# RGB.net
KiCad netlist of a schematic drawn in Altium Designer
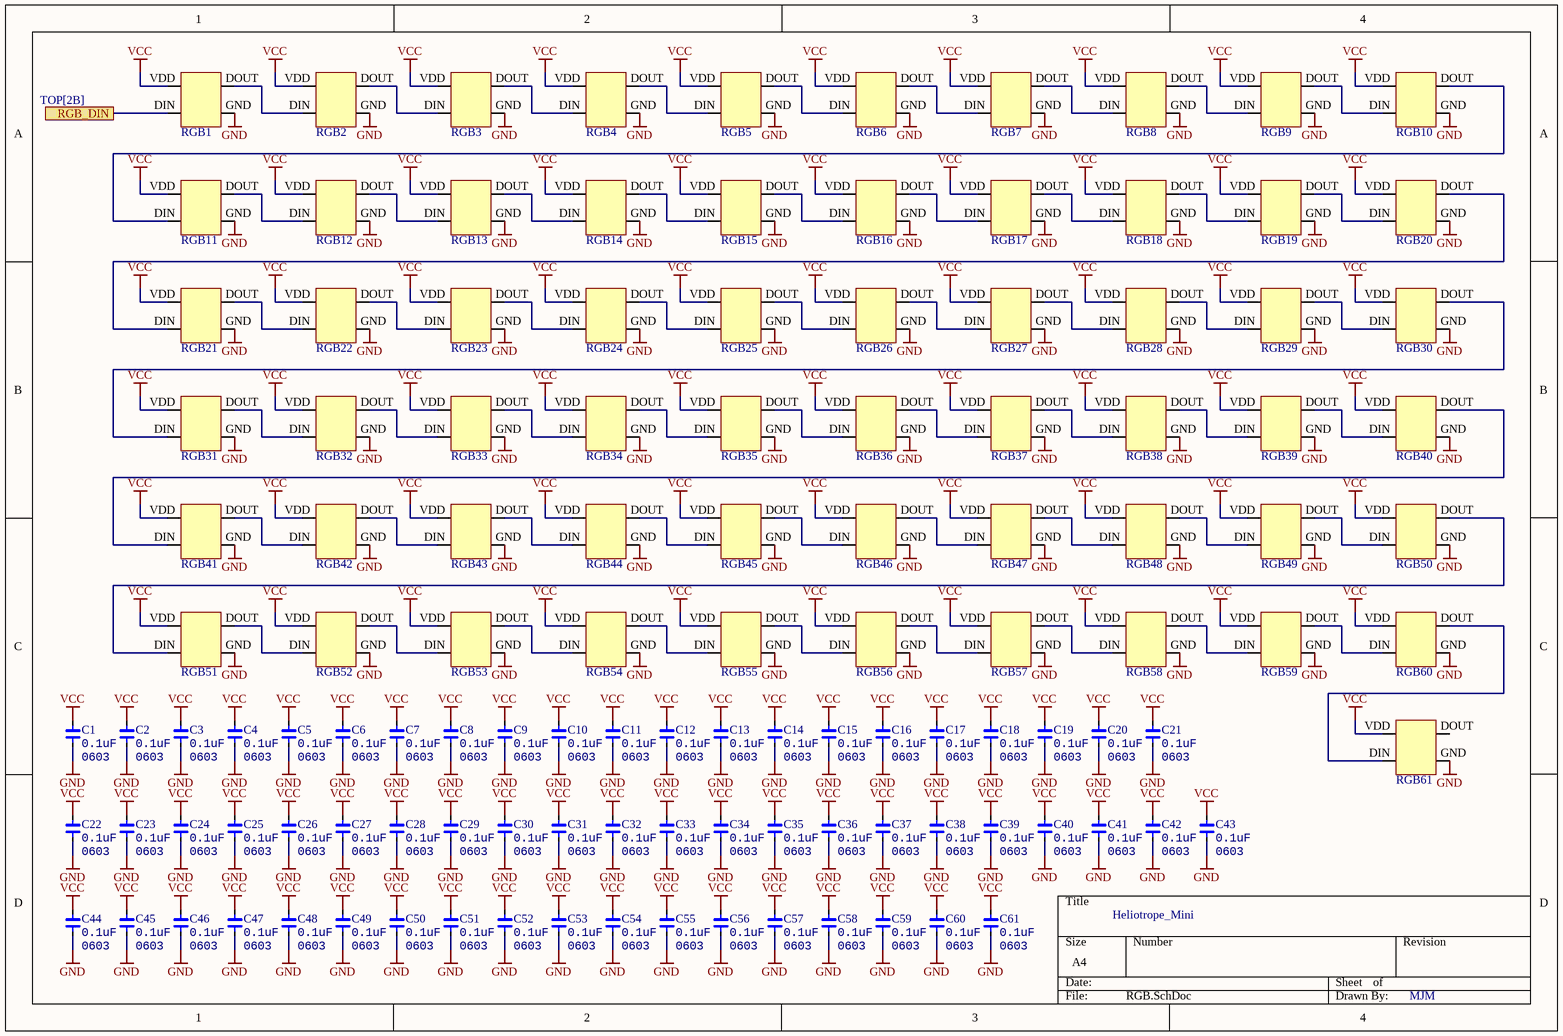
[diagram p0: RGB.SchDoc]

(export (version "E")
  (design (tool "Eeschema 10.0.6"))
  (components
    (comp (ref "C1")
      (value "0.1uF")
      (footprint "FP-CC0603-DA-MFG")
      (description "0603 0.1 uF 50 V ±5 % Tolerance X7R SMT Multilayer Ceramic Capacitor")
      (fields (field (name "TYPE") "0603") (field (name "Comment") "CC0603JRX7R9BB104"))
      (libsource (lib "Microcom Corporation") (part "M_Cap"))
    )
    (comp (ref "C2")
      (value "0.1uF")
      (footprint "FP-CC0603-DA-MFG")
      (description "0603 0.1 uF 50 V ±5 % Tolerance X7R SMT Multilayer Ceramic Capacitor")
      (fields (field (name "TYPE") "0603") (field (name "Comment") "CC0603JRX7R9BB104"))
      (libsource (lib "Microcom Corporation") (part "M_Cap"))
    )
    (comp (ref "C3")
      (value "0.1uF")
      (footprint "FP-CC0603-DA-MFG")
      (description "0603 0.1 uF 50 V ±5 % Tolerance X7R SMT Multilayer Ceramic Capacitor")
      (fields (field (name "TYPE") "0603") (field (name "Comment") "CC0603JRX7R9BB104"))
      (libsource (lib "Microcom Corporation") (part "M_Cap"))
    )
    (comp (ref "C4")
      (value "0.1uF")
      (footprint "FP-CC0603-DA-MFG")
      (description "0603 0.1 uF 50 V ±5 % Tolerance X7R SMT Multilayer Ceramic Capacitor")
      (fields (field (name "TYPE") "0603") (field (name "Comment") "CC0603JRX7R9BB104"))
      (libsource (lib "Microcom Corporation") (part "M_Cap"))
    )
    (comp (ref "C5")
      (value "0.1uF")
      (footprint "FP-CC0603-DA-MFG")
      (description "0603 0.1 uF 50 V ±5 % Tolerance X7R SMT Multilayer Ceramic Capacitor")
      (fields (field (name "TYPE") "0603") (field (name "Comment") "CC0603JRX7R9BB104"))
      (libsource (lib "Microcom Corporation") (part "M_Cap"))
    )
    (comp (ref "C6")
      (value "0.1uF")
      (footprint "FP-CC0603-DA-MFG")
      (description "0603 0.1 uF 50 V ±5 % Tolerance X7R SMT Multilayer Ceramic Capacitor")
      (fields (field (name "TYPE") "0603") (field (name "Comment") "CC0603JRX7R9BB104"))
      (libsource (lib "Microcom Corporation") (part "M_Cap"))
    )
    (comp (ref "C7")
      (value "0.1uF")
      (footprint "FP-CC0603-DA-MFG")
      (description "0603 0.1 uF 50 V ±5 % Tolerance X7R SMT Multilayer Ceramic Capacitor")
      (fields (field (name "TYPE") "0603") (field (name "Comment") "CC0603JRX7R9BB104"))
      (libsource (lib "Microcom Corporation") (part "M_Cap"))
    )
    (comp (ref "C8")
      (value "0.1uF")
      (footprint "FP-CC0603-DA-MFG")
      (description "0603 0.1 uF 50 V ±5 % Tolerance X7R SMT Multilayer Ceramic Capacitor")
      (fields (field (name "TYPE") "0603") (field (name "Comment") "CC0603JRX7R9BB104"))
      (libsource (lib "Microcom Corporation") (part "M_Cap"))
    )
    (comp (ref "C9")
      (value "0.1uF")
      (footprint "FP-CC0603-DA-MFG")
      (description "0603 0.1 uF 50 V ±5 % Tolerance X7R SMT Multilayer Ceramic Capacitor")
      (fields (field (name "TYPE") "0603") (field (name "Comment") "CC0603JRX7R9BB104"))
      (libsource (lib "Microcom Corporation") (part "M_Cap"))
    )
    (comp (ref "C10")
      (value "0.1uF")
      (footprint "FP-CC0603-DA-MFG")
      (description "0603 0.1 uF 50 V ±5 % Tolerance X7R SMT Multilayer Ceramic Capacitor")
      (fields (field (name "TYPE") "0603") (field (name "Comment") "CC0603JRX7R9BB104"))
      (libsource (lib "Microcom Corporation") (part "M_Cap"))
    )
    (comp (ref "C11")
      (value "0.1uF")
      (footprint "FP-CC0603-DA-MFG")
      (description "0603 0.1 uF 50 V ±5 % Tolerance X7R SMT Multilayer Ceramic Capacitor")
      (fields (field (name "TYPE") "0603") (field (name "Comment") "CC0603JRX7R9BB104"))
      (libsource (lib "Microcom Corporation") (part "M_Cap"))
    )
    (comp (ref "C12")
      (value "0.1uF")
      (footprint "FP-CC0603-DA-MFG")
      (description "0603 0.1 uF 50 V ±5 % Tolerance X7R SMT Multilayer Ceramic Capacitor")
      (fields (field (name "TYPE") "0603") (field (name "Comment") "CC0603JRX7R9BB104"))
      (libsource (lib "Microcom Corporation") (part "M_Cap"))
    )
    (comp (ref "C13")
      (value "0.1uF")
      (footprint "FP-CC0603-DA-MFG")
      (description "0603 0.1 uF 50 V ±5 % Tolerance X7R SMT Multilayer Ceramic Capacitor")
      (fields (field (name "TYPE") "0603") (field (name "Comment") "CC0603JRX7R9BB104"))
      (libsource (lib "Microcom Corporation") (part "M_Cap"))
    )
    (comp (ref "C14")
      (value "0.1uF")
      (footprint "FP-CC0603-DA-MFG")
      (description "0603 0.1 uF 50 V ±5 % Tolerance X7R SMT Multilayer Ceramic Capacitor")
      (fields (field (name "TYPE") "0603") (field (name "Comment") "CC0603JRX7R9BB104"))
      (libsource (lib "Microcom Corporation") (part "M_Cap"))
    )
    (comp (ref "C15")
      (value "0.1uF")
      (footprint "FP-CC0603-DA-MFG")
      (description "0603 0.1 uF 50 V ±5 % Tolerance X7R SMT Multilayer Ceramic Capacitor")
      (fields (field (name "TYPE") "0603") (field (name "Comment") "CC0603JRX7R9BB104"))
      (libsource (lib "Microcom Corporation") (part "M_Cap"))
    )
    (comp (ref "C16")
      (value "0.1uF")
      (footprint "FP-CC0603-DA-MFG")
      (description "0603 0.1 uF 50 V ±5 % Tolerance X7R SMT Multilayer Ceramic Capacitor")
      (fields (field (name "TYPE") "0603") (field (name "Comment") "CC0603JRX7R9BB104"))
      (libsource (lib "Microcom Corporation") (part "M_Cap"))
    )
    (comp (ref "C17")
      (value "0.1uF")
      (footprint "FP-CC0603-DA-MFG")
      (description "0603 0.1 uF 50 V ±5 % Tolerance X7R SMT Multilayer Ceramic Capacitor")
      (fields (field (name "TYPE") "0603") (field (name "Comment") "CC0603JRX7R9BB104"))
      (libsource (lib "Microcom Corporation") (part "M_Cap"))
    )
    (comp (ref "C18")
      (value "0.1uF")
      (footprint "FP-CC0603-DA-MFG")
      (description "0603 0.1 uF 50 V ±5 % Tolerance X7R SMT Multilayer Ceramic Capacitor")
      (fields (field (name "TYPE") "0603") (field (name "Comment") "CC0603JRX7R9BB104"))
      (libsource (lib "Microcom Corporation") (part "M_Cap"))
    )
    (comp (ref "C19")
      (value "0.1uF")
      (footprint "FP-CC0603-DA-MFG")
      (description "0603 0.1 uF 50 V ±5 % Tolerance X7R SMT Multilayer Ceramic Capacitor")
      (fields (field (name "TYPE") "0603") (field (name "Comment") "CC0603JRX7R9BB104"))
      (libsource (lib "Microcom Corporation") (part "M_Cap"))
    )
    (comp (ref "C20")
      (value "0.1uF")
      (footprint "FP-CC0603-DA-MFG")
      (description "0603 0.1 uF 50 V ±5 % Tolerance X7R SMT Multilayer Ceramic Capacitor")
      (fields (field (name "TYPE") "0603") (field (name "Comment") "CC0603JRX7R9BB104"))
      (libsource (lib "Microcom Corporation") (part "M_Cap"))
    )
    (comp (ref "C21")
      (value "0.1uF")
      (footprint "FP-CC0603-DA-MFG")
      (description "0603 0.1 uF 50 V ±5 % Tolerance X7R SMT Multilayer Ceramic Capacitor")
      (fields (field (name "TYPE") "0603") (field (name "Comment") "CC0603JRX7R9BB104"))
      (libsource (lib "Microcom Corporation") (part "M_Cap"))
    )
    (comp (ref "C22")
      (value "0.1uF")
      (footprint "FP-CC0603-DA-MFG")
      (description "0603 0.1 uF 50 V ±5 % Tolerance X7R SMT Multilayer Ceramic Capacitor")
      (fields (field (name "TYPE") "0603") (field (name "Comment") "CC0603JRX7R9BB104"))
      (libsource (lib "Microcom Corporation") (part "M_Cap"))
    )
    (comp (ref "C23")
      (value "0.1uF")
      (footprint "FP-CC0603-DA-MFG")
      (description "0603 0.1 uF 50 V ±5 % Tolerance X7R SMT Multilayer Ceramic Capacitor")
      (fields (field (name "TYPE") "0603") (field (name "Comment") "CC0603JRX7R9BB104"))
      (libsource (lib "Microcom Corporation") (part "M_Cap"))
    )
    (comp (ref "C24")
      (value "0.1uF")
      (footprint "FP-CC0603-DA-MFG")
      (description "0603 0.1 uF 50 V ±5 % Tolerance X7R SMT Multilayer Ceramic Capacitor")
      (fields (field (name "TYPE") "0603") (field (name "Comment") "CC0603JRX7R9BB104"))
      (libsource (lib "Microcom Corporation") (part "M_Cap"))
    )
    (comp (ref "C25")
      (value "0.1uF")
      (footprint "FP-CC0603-DA-MFG")
      (description "0603 0.1 uF 50 V ±5 % Tolerance X7R SMT Multilayer Ceramic Capacitor")
      (fields (field (name "TYPE") "0603") (field (name "Comment") "CC0603JRX7R9BB104"))
      (libsource (lib "Microcom Corporation") (part "M_Cap"))
    )
    (comp (ref "C26")
      (value "0.1uF")
      (footprint "FP-CC0603-DA-MFG")
      (description "0603 0.1 uF 50 V ±5 % Tolerance X7R SMT Multilayer Ceramic Capacitor")
      (fields (field (name "TYPE") "0603") (field (name "Comment") "CC0603JRX7R9BB104"))
      (libsource (lib "Microcom Corporation") (part "M_Cap"))
    )
    (comp (ref "C27")
      (value "0.1uF")
      (footprint "FP-CC0603-DA-MFG")
      (description "0603 0.1 uF 50 V ±5 % Tolerance X7R SMT Multilayer Ceramic Capacitor")
      (fields (field (name "TYPE") "0603") (field (name "Comment") "CC0603JRX7R9BB104"))
      (libsource (lib "Microcom Corporation") (part "M_Cap"))
    )
    (comp (ref "C28")
      (value "0.1uF")
      (footprint "FP-CC0603-DA-MFG")
      (description "0603 0.1 uF 50 V ±5 % Tolerance X7R SMT Multilayer Ceramic Capacitor")
      (fields (field (name "TYPE") "0603") (field (name "Comment") "CC0603JRX7R9BB104"))
      (libsource (lib "Microcom Corporation") (part "M_Cap"))
    )
    (comp (ref "C29")
      (value "0.1uF")
      (footprint "FP-CC0603-DA-MFG")
      (description "0603 0.1 uF 50 V ±5 % Tolerance X7R SMT Multilayer Ceramic Capacitor")
      (fields (field (name "TYPE") "0603") (field (name "Comment") "CC0603JRX7R9BB104"))
      (libsource (lib "Microcom Corporation") (part "M_Cap"))
    )
    (comp (ref "C30")
      (value "0.1uF")
      (footprint "FP-CC0603-DA-MFG")
      (description "0603 0.1 uF 50 V ±5 % Tolerance X7R SMT Multilayer Ceramic Capacitor")
      (fields (field (name "TYPE") "0603") (field (name "Comment") "CC0603JRX7R9BB104"))
      (libsource (lib "Microcom Corporation") (part "M_Cap"))
    )
    (comp (ref "C31")
      (value "0.1uF")
      (footprint "FP-CC0603-DA-MFG")
      (description "0603 0.1 uF 50 V ±5 % Tolerance X7R SMT Multilayer Ceramic Capacitor")
      (fields (field (name "TYPE") "0603") (field (name "Comment") "CC0603JRX7R9BB104"))
      (libsource (lib "Microcom Corporation") (part "M_Cap"))
    )
    (comp (ref "C32")
      (value "0.1uF")
      (footprint "FP-CC0603-DA-MFG")
      (description "0603 0.1 uF 50 V ±5 % Tolerance X7R SMT Multilayer Ceramic Capacitor")
      (fields (field (name "TYPE") "0603") (field (name "Comment") "CC0603JRX7R9BB104"))
      (libsource (lib "Microcom Corporation") (part "M_Cap"))
    )
    (comp (ref "C33")
      (value "0.1uF")
      (footprint "FP-CC0603-DA-MFG")
      (description "0603 0.1 uF 50 V ±5 % Tolerance X7R SMT Multilayer Ceramic Capacitor")
      (fields (field (name "TYPE") "0603") (field (name "Comment") "CC0603JRX7R9BB104"))
      (libsource (lib "Microcom Corporation") (part "M_Cap"))
    )
    (comp (ref "C34")
      (value "0.1uF")
      (footprint "FP-CC0603-DA-MFG")
      (description "0603 0.1 uF 50 V ±5 % Tolerance X7R SMT Multilayer Ceramic Capacitor")
      (fields (field (name "TYPE") "0603") (field (name "Comment") "CC0603JRX7R9BB104"))
      (libsource (lib "Microcom Corporation") (part "M_Cap"))
    )
    (comp (ref "C35")
      (value "0.1uF")
      (footprint "FP-CC0603-DA-MFG")
      (description "0603 0.1 uF 50 V ±5 % Tolerance X7R SMT Multilayer Ceramic Capacitor")
      (fields (field (name "TYPE") "0603") (field (name "Comment") "CC0603JRX7R9BB104"))
      (libsource (lib "Microcom Corporation") (part "M_Cap"))
    )
    (comp (ref "C36")
      (value "0.1uF")
      (footprint "FP-CC0603-DA-MFG")
      (description "0603 0.1 uF 50 V ±5 % Tolerance X7R SMT Multilayer Ceramic Capacitor")
      (fields (field (name "TYPE") "0603") (field (name "Comment") "CC0603JRX7R9BB104"))
      (libsource (lib "Microcom Corporation") (part "M_Cap"))
    )
    (comp (ref "C37")
      (value "0.1uF")
      (footprint "FP-CC0603-DA-MFG")
      (description "0603 0.1 uF 50 V ±5 % Tolerance X7R SMT Multilayer Ceramic Capacitor")
      (fields (field (name "TYPE") "0603") (field (name "Comment") "CC0603JRX7R9BB104"))
      (libsource (lib "Microcom Corporation") (part "M_Cap"))
    )
    (comp (ref "C38")
      (value "0.1uF")
      (footprint "FP-CC0603-DA-MFG")
      (description "0603 0.1 uF 50 V ±5 % Tolerance X7R SMT Multilayer Ceramic Capacitor")
      (fields (field (name "TYPE") "0603") (field (name "Comment") "CC0603JRX7R9BB104"))
      (libsource (lib "Microcom Corporation") (part "M_Cap"))
    )
    (comp (ref "C39")
      (value "0.1uF")
      (footprint "FP-CC0603-DA-MFG")
      (description "0603 0.1 uF 50 V ±5 % Tolerance X7R SMT Multilayer Ceramic Capacitor")
      (fields (field (name "TYPE") "0603") (field (name "Comment") "CC0603JRX7R9BB104"))
      (libsource (lib "Microcom Corporation") (part "M_Cap"))
    )
    (comp (ref "C40")
      (value "0.1uF")
      (footprint "FP-CC0603-DA-MFG")
      (description "0603 0.1 uF 50 V ±5 % Tolerance X7R SMT Multilayer Ceramic Capacitor")
      (fields (field (name "TYPE") "0603") (field (name "Comment") "CC0603JRX7R9BB104"))
      (libsource (lib "Microcom Corporation") (part "M_Cap"))
    )
    (comp (ref "C41")
      (value "0.1uF")
      (footprint "FP-CC0603-DA-MFG")
      (description "0603 0.1 uF 50 V ±5 % Tolerance X7R SMT Multilayer Ceramic Capacitor")
      (fields (field (name "TYPE") "0603") (field (name "Comment") "CC0603JRX7R9BB104"))
      (libsource (lib "Microcom Corporation") (part "M_Cap"))
    )
    (comp (ref "C42")
      (value "0.1uF")
      (footprint "FP-CC0603-DA-MFG")
      (description "0603 0.1 uF 50 V ±5 % Tolerance X7R SMT Multilayer Ceramic Capacitor")
      (fields (field (name "TYPE") "0603") (field (name "Comment") "CC0603JRX7R9BB104"))
      (libsource (lib "Microcom Corporation") (part "M_Cap"))
    )
    (comp (ref "C43")
      (value "0.1uF")
      (footprint "FP-CC0603-DA-MFG")
      (description "0603 0.1 uF 50 V ±5 % Tolerance X7R SMT Multilayer Ceramic Capacitor")
      (fields (field (name "TYPE") "0603") (field (name "Comment") "CC0603JRX7R9BB104"))
      (libsource (lib "Microcom Corporation") (part "M_Cap"))
    )
    (comp (ref "C44")
      (value "0.1uF")
      (footprint "FP-CC0603-DA-MFG")
      (description "0603 0.1 uF 50 V ±5 % Tolerance X7R SMT Multilayer Ceramic Capacitor")
      (fields (field (name "TYPE") "0603") (field (name "Comment") "CC0603JRX7R9BB104"))
      (libsource (lib "Microcom Corporation") (part "M_Cap"))
    )
    (comp (ref "C45")
      (value "0.1uF")
      (footprint "FP-CC0603-DA-MFG")
      (description "0603 0.1 uF 50 V ±5 % Tolerance X7R SMT Multilayer Ceramic Capacitor")
      (fields (field (name "TYPE") "0603") (field (name "Comment") "CC0603JRX7R9BB104"))
      (libsource (lib "Microcom Corporation") (part "M_Cap"))
    )
    (comp (ref "C46")
      (value "0.1uF")
      (footprint "FP-CC0603-DA-MFG")
      (description "0603 0.1 uF 50 V ±5 % Tolerance X7R SMT Multilayer Ceramic Capacitor")
      (fields (field (name "TYPE") "0603") (field (name "Comment") "CC0603JRX7R9BB104"))
      (libsource (lib "Microcom Corporation") (part "M_Cap"))
    )
    (comp (ref "C47")
      (value "0.1uF")
      (footprint "FP-CC0603-DA-MFG")
      (description "0603 0.1 uF 50 V ±5 % Tolerance X7R SMT Multilayer Ceramic Capacitor")
      (fields (field (name "TYPE") "0603") (field (name "Comment") "CC0603JRX7R9BB104"))
      (libsource (lib "Microcom Corporation") (part "M_Cap"))
    )
    (comp (ref "C48")
      (value "0.1uF")
      (footprint "FP-CC0603-DA-MFG")
      (description "0603 0.1 uF 50 V ±5 % Tolerance X7R SMT Multilayer Ceramic Capacitor")
      (fields (field (name "TYPE") "0603") (field (name "Comment") "CC0603JRX7R9BB104"))
      (libsource (lib "Microcom Corporation") (part "M_Cap"))
    )
    (comp (ref "C49")
      (value "0.1uF")
      (footprint "FP-CC0603-DA-MFG")
      (description "0603 0.1 uF 50 V ±5 % Tolerance X7R SMT Multilayer Ceramic Capacitor")
      (fields (field (name "TYPE") "0603") (field (name "Comment") "CC0603JRX7R9BB104"))
      (libsource (lib "Microcom Corporation") (part "M_Cap"))
    )
    (comp (ref "C50")
      (value "0.1uF")
      (footprint "FP-CC0603-DA-MFG")
      (description "0603 0.1 uF 50 V ±5 % Tolerance X7R SMT Multilayer Ceramic Capacitor")
      (fields (field (name "TYPE") "0603") (field (name "Comment") "CC0603JRX7R9BB104"))
      (libsource (lib "Microcom Corporation") (part "M_Cap"))
    )
    (comp (ref "C51")
      (value "0.1uF")
      (footprint "FP-CC0603-DA-MFG")
      (description "0603 0.1 uF 50 V ±5 % Tolerance X7R SMT Multilayer Ceramic Capacitor")
      (fields (field (name "TYPE") "0603") (field (name "Comment") "CC0603JRX7R9BB104"))
      (libsource (lib "Microcom Corporation") (part "M_Cap"))
    )
    (comp (ref "C52")
      (value "0.1uF")
      (footprint "FP-CC0603-DA-MFG")
      (description "0603 0.1 uF 50 V ±5 % Tolerance X7R SMT Multilayer Ceramic Capacitor")
      (fields (field (name "TYPE") "0603") (field (name "Comment") "CC0603JRX7R9BB104"))
      (libsource (lib "Microcom Corporation") (part "M_Cap"))
    )
    (comp (ref "C53")
      (value "0.1uF")
      (footprint "FP-CC0603-DA-MFG")
      (description "0603 0.1 uF 50 V ±5 % Tolerance X7R SMT Multilayer Ceramic Capacitor")
      (fields (field (name "TYPE") "0603") (field (name "Comment") "CC0603JRX7R9BB104"))
      (libsource (lib "Microcom Corporation") (part "M_Cap"))
    )
    (comp (ref "C54")
      (value "0.1uF")
      (footprint "FP-CC0603-DA-MFG")
      (description "0603 0.1 uF 50 V ±5 % Tolerance X7R SMT Multilayer Ceramic Capacitor")
      (fields (field (name "TYPE") "0603") (field (name "Comment") "CC0603JRX7R9BB104"))
      (libsource (lib "Microcom Corporation") (part "M_Cap"))
    )
    (comp (ref "C55")
      (value "0.1uF")
      (footprint "FP-CC0603-DA-MFG")
      (description "0603 0.1 uF 50 V ±5 % Tolerance X7R SMT Multilayer Ceramic Capacitor")
      (fields (field (name "TYPE") "0603") (field (name "Comment") "CC0603JRX7R9BB104"))
      (libsource (lib "Microcom Corporation") (part "M_Cap"))
    )
    (comp (ref "C56")
      (value "0.1uF")
      (footprint "FP-CC0603-DA-MFG")
      (description "0603 0.1 uF 50 V ±5 % Tolerance X7R SMT Multilayer Ceramic Capacitor")
      (fields (field (name "TYPE") "0603") (field (name "Comment") "CC0603JRX7R9BB104"))
      (libsource (lib "Microcom Corporation") (part "M_Cap"))
    )
    (comp (ref "C57")
      (value "0.1uF")
      (footprint "FP-CC0603-DA-MFG")
      (description "0603 0.1 uF 50 V ±5 % Tolerance X7R SMT Multilayer Ceramic Capacitor")
      (fields (field (name "TYPE") "0603") (field (name "Comment") "CC0603JRX7R9BB104"))
      (libsource (lib "Microcom Corporation") (part "M_Cap"))
    )
    (comp (ref "C58")
      (value "0.1uF")
      (footprint "FP-CC0603-DA-MFG")
      (description "0603 0.1 uF 50 V ±5 % Tolerance X7R SMT Multilayer Ceramic Capacitor")
      (fields (field (name "TYPE") "0603") (field (name "Comment") "CC0603JRX7R9BB104"))
      (libsource (lib "Microcom Corporation") (part "M_Cap"))
    )
    (comp (ref "C59")
      (value "0.1uF")
      (footprint "FP-CC0603-DA-MFG")
      (description "0603 0.1 uF 50 V ±5 % Tolerance X7R SMT Multilayer Ceramic Capacitor")
      (fields (field (name "TYPE") "0603") (field (name "Comment") "CC0603JRX7R9BB104"))
      (libsource (lib "Microcom Corporation") (part "M_Cap"))
    )
    (comp (ref "C60")
      (value "0.1uF")
      (footprint "FP-CC0603-DA-MFG")
      (description "0603 0.1 uF 50 V ±5 % Tolerance X7R SMT Multilayer Ceramic Capacitor")
      (fields (field (name "TYPE") "0603") (field (name "Comment") "CC0603JRX7R9BB104"))
      (libsource (lib "Microcom Corporation") (part "M_Cap"))
    )
    (comp (ref "C61")
      (value "0.1uF")
      (footprint "FP-CC0603-DA-MFG")
      (description "0603 0.1 uF 50 V ±5 % Tolerance X7R SMT Multilayer Ceramic Capacitor")
      (fields (field (name "TYPE") "0603") (field (name "Comment") "CC0603JRX7R9BB104"))
      (libsource (lib "Microcom Corporation") (part "M_Cap"))
    )
    (comp (ref "RGB1")
      (value "SK6812MINI-E")
      (footprint "sk6812minie")
      (libsource (lib "Microcom Corporation") (part "SK6812MINI-E"))
    )
    (comp (ref "RGB2")
      (value "SK6812MINI-E")
      (footprint "sk6812minie")
      (libsource (lib "Microcom Corporation") (part "SK6812MINI-E"))
    )
    (comp (ref "RGB3")
      (value "SK6812MINI-E")
      (footprint "sk6812minie")
      (libsource (lib "Microcom Corporation") (part "SK6812MINI-E"))
    )
    (comp (ref "RGB4")
      (value "SK6812MINI-E")
      (footprint "sk6812minie")
      (libsource (lib "Microcom Corporation") (part "SK6812MINI-E"))
    )
    (comp (ref "RGB5")
      (value "SK6812MINI-E")
      (footprint "sk6812minie")
      (libsource (lib "Microcom Corporation") (part "SK6812MINI-E"))
    )
    (comp (ref "RGB6")
      (value "SK6812MINI-E")
      (footprint "sk6812minie")
      (libsource (lib "Microcom Corporation") (part "SK6812MINI-E"))
    )
    (comp (ref "RGB7")
      (value "SK6812MINI-E")
      (footprint "sk6812minie")
      (libsource (lib "Microcom Corporation") (part "SK6812MINI-E"))
    )
    (comp (ref "RGB8")
      (value "SK6812MINI-E")
      (footprint "sk6812minie")
      (libsource (lib "Microcom Corporation") (part "SK6812MINI-E"))
    )
    (comp (ref "RGB9")
      (value "SK6812MINI-E")
      (footprint "sk6812minie")
      (libsource (lib "Microcom Corporation") (part "SK6812MINI-E"))
    )
    (comp (ref "RGB10")
      (value "SK6812MINI-E")
      (footprint "sk6812minie")
      (libsource (lib "Microcom Corporation") (part "SK6812MINI-E"))
    )
    (comp (ref "RGB11")
      (value "SK6812MINI-E")
      (footprint "sk6812minie")
      (libsource (lib "Microcom Corporation") (part "SK6812MINI-E"))
    )
    (comp (ref "RGB12")
      (value "SK6812MINI-E")
      (footprint "sk6812minie")
      (libsource (lib "Microcom Corporation") (part "SK6812MINI-E"))
    )
    (comp (ref "RGB13")
      (value "SK6812MINI-E")
      (footprint "sk6812minie")
      (libsource (lib "Microcom Corporation") (part "SK6812MINI-E"))
    )
    (comp (ref "RGB14")
      (value "SK6812MINI-E")
      (footprint "sk6812minie")
      (libsource (lib "Microcom Corporation") (part "SK6812MINI-E"))
    )
    (comp (ref "RGB15")
      (value "SK6812MINI-E")
      (footprint "sk6812minie")
      (libsource (lib "Microcom Corporation") (part "SK6812MINI-E"))
    )
    (comp (ref "RGB16")
      (value "SK6812MINI-E")
      (footprint "sk6812minie")
      (libsource (lib "Microcom Corporation") (part "SK6812MINI-E"))
    )
    (comp (ref "RGB17")
      (value "SK6812MINI-E")
      (footprint "sk6812minie")
      (libsource (lib "Microcom Corporation") (part "SK6812MINI-E"))
    )
    (comp (ref "RGB18")
      (value "SK6812MINI-E")
      (footprint "sk6812minie")
      (libsource (lib "Microcom Corporation") (part "SK6812MINI-E"))
    )
    (comp (ref "RGB19")
      (value "SK6812MINI-E")
      (footprint "sk6812minie")
      (libsource (lib "Microcom Corporation") (part "SK6812MINI-E"))
    )
    (comp (ref "RGB20")
      (value "SK6812MINI-E")
      (footprint "sk6812minie")
      (libsource (lib "Microcom Corporation") (part "SK6812MINI-E"))
    )
    (comp (ref "RGB21")
      (value "SK6812MINI-E")
      (footprint "sk6812minie")
      (libsource (lib "Microcom Corporation") (part "SK6812MINI-E"))
    )
    (comp (ref "RGB22")
      (value "SK6812MINI-E")
      (footprint "sk6812minie")
      (libsource (lib "Microcom Corporation") (part "SK6812MINI-E"))
    )
    (comp (ref "RGB23")
      (value "SK6812MINI-E")
      (footprint "sk6812minie")
      (libsource (lib "Microcom Corporation") (part "SK6812MINI-E"))
    )
    (comp (ref "RGB24")
      (value "SK6812MINI-E")
      (footprint "sk6812minie")
      (libsource (lib "Microcom Corporation") (part "SK6812MINI-E"))
    )
    (comp (ref "RGB25")
      (value "SK6812MINI-E")
      (footprint "sk6812minie")
      (libsource (lib "Microcom Corporation") (part "SK6812MINI-E"))
    )
    (comp (ref "RGB26")
      (value "SK6812MINI-E")
      (footprint "sk6812minie")
      (libsource (lib "Microcom Corporation") (part "SK6812MINI-E"))
    )
    (comp (ref "RGB27")
      (value "SK6812MINI-E")
      (footprint "sk6812minie")
      (libsource (lib "Microcom Corporation") (part "SK6812MINI-E"))
    )
    (comp (ref "RGB28")
      (value "SK6812MINI-E")
      (footprint "sk6812minie")
      (libsource (lib "Microcom Corporation") (part "SK6812MINI-E"))
    )
    (comp (ref "RGB29")
      (value "SK6812MINI-E")
      (footprint "sk6812minie")
      (libsource (lib "Microcom Corporation") (part "SK6812MINI-E"))
    )
    (comp (ref "RGB30")
      (value "SK6812MINI-E")
      (footprint "sk6812minie")
      (libsource (lib "Microcom Corporation") (part "SK6812MINI-E"))
    )
    (comp (ref "RGB31")
      (value "SK6812MINI-E")
      (footprint "sk6812minie")
      (libsource (lib "Microcom Corporation") (part "SK6812MINI-E"))
    )
    (comp (ref "RGB32")
      (value "SK6812MINI-E")
      (footprint "sk6812minie")
      (libsource (lib "Microcom Corporation") (part "SK6812MINI-E"))
    )
    (comp (ref "RGB33")
      (value "SK6812MINI-E")
      (footprint "sk6812minie")
      (libsource (lib "Microcom Corporation") (part "SK6812MINI-E"))
    )
    (comp (ref "RGB34")
      (value "SK6812MINI-E")
      (footprint "sk6812minie")
      (libsource (lib "Microcom Corporation") (part "SK6812MINI-E"))
    )
    (comp (ref "RGB35")
      (value "SK6812MINI-E")
      (footprint "sk6812minie")
      (libsource (lib "Microcom Corporation") (part "SK6812MINI-E"))
    )
    (comp (ref "RGB36")
      (value "SK6812MINI-E")
      (footprint "sk6812minie")
      (libsource (lib "Microcom Corporation") (part "SK6812MINI-E"))
    )
    (comp (ref "RGB37")
      (value "SK6812MINI-E")
      (footprint "sk6812minie")
      (libsource (lib "Microcom Corporation") (part "SK6812MINI-E"))
    )
    (comp (ref "RGB38")
      (value "SK6812MINI-E")
      (footprint "sk6812minie")
      (libsource (lib "Microcom Corporation") (part "SK6812MINI-E"))
    )
    (comp (ref "RGB39")
      (value "SK6812MINI-E")
      (footprint "sk6812minie")
      (libsource (lib "Microcom Corporation") (part "SK6812MINI-E"))
    )
    (comp (ref "RGB40")
      (value "SK6812MINI-E")
      (footprint "sk6812minie")
      (libsource (lib "Microcom Corporation") (part "SK6812MINI-E"))
    )
    (comp (ref "RGB41")
      (value "SK6812MINI-E")
      (footprint "sk6812minie")
      (libsource (lib "Microcom Corporation") (part "SK6812MINI-E"))
    )
    (comp (ref "RGB42")
      (value "SK6812MINI-E")
      (footprint "sk6812minie")
      (libsource (lib "Microcom Corporation") (part "SK6812MINI-E"))
    )
    (comp (ref "RGB43")
      (value "SK6812MINI-E")
      (footprint "sk6812minie")
      (libsource (lib "Microcom Corporation") (part "SK6812MINI-E"))
    )
    (comp (ref "RGB44")
      (value "SK6812MINI-E")
      (footprint "sk6812minie")
      (libsource (lib "Microcom Corporation") (part "SK6812MINI-E"))
    )
    (comp (ref "RGB45")
      (value "SK6812MINI-E")
      (footprint "sk6812minie")
      (libsource (lib "Microcom Corporation") (part "SK6812MINI-E"))
    )
    (comp (ref "RGB46")
      (value "SK6812MINI-E")
      (footprint "sk6812minie")
      (libsource (lib "Microcom Corporation") (part "SK6812MINI-E"))
    )
    (comp (ref "RGB47")
      (value "SK6812MINI-E")
      (footprint "sk6812minie")
      (libsource (lib "Microcom Corporation") (part "SK6812MINI-E"))
    )
    (comp (ref "RGB48")
      (value "SK6812MINI-E")
      (footprint "sk6812minie")
      (libsource (lib "Microcom Corporation") (part "SK6812MINI-E"))
    )
    (comp (ref "RGB49")
      (value "SK6812MINI-E")
      (footprint "sk6812minie")
      (libsource (lib "Microcom Corporation") (part "SK6812MINI-E"))
    )
    (comp (ref "RGB50")
      (value "SK6812MINI-E")
      (footprint "sk6812minie")
      (libsource (lib "Microcom Corporation") (part "SK6812MINI-E"))
    )
    (comp (ref "RGB51")
      (value "SK6812MINI-E")
      (footprint "sk6812minie")
      (libsource (lib "Microcom Corporation") (part "SK6812MINI-E"))
    )
    (comp (ref "RGB52")
      (value "SK6812MINI-E")
      (footprint "sk6812minie")
      (libsource (lib "Microcom Corporation") (part "SK6812MINI-E"))
    )
    (comp (ref "RGB53")
      (value "SK6812MINI-E")
      (footprint "sk6812minie")
      (libsource (lib "Microcom Corporation") (part "SK6812MINI-E"))
    )
    (comp (ref "RGB54")
      (value "SK6812MINI-E")
      (footprint "sk6812minie")
      (libsource (lib "Microcom Corporation") (part "SK6812MINI-E"))
    )
    (comp (ref "RGB55")
      (value "SK6812MINI-E")
      (footprint "sk6812minie")
      (libsource (lib "Microcom Corporation") (part "SK6812MINI-E"))
    )
    (comp (ref "RGB56")
      (value "SK6812MINI-E")
      (footprint "sk6812minie")
      (libsource (lib "Microcom Corporation") (part "SK6812MINI-E"))
    )
    (comp (ref "RGB57")
      (value "SK6812MINI-E")
      (footprint "sk6812minie")
      (libsource (lib "Microcom Corporation") (part "SK6812MINI-E"))
    )
    (comp (ref "RGB58")
      (value "SK6812MINI-E")
      (footprint "sk6812minie")
      (libsource (lib "Microcom Corporation") (part "SK6812MINI-E"))
    )
    (comp (ref "RGB59")
      (value "SK6812MINI-E")
      (footprint "sk6812minie")
      (libsource (lib "Microcom Corporation") (part "SK6812MINI-E"))
    )
    (comp (ref "RGB60")
      (value "SK6812MINI-E")
      (footprint "sk6812minie")
      (libsource (lib "Microcom Corporation") (part "SK6812MINI-E"))
    )
    (comp (ref "RGB61")
      (value "SK6812MINI-E")
      (footprint "sk6812minie")
      (libsource (lib "Microcom Corporation") (part "SK6812MINI-E"))
    )
  )
  (nets
    (net (code "1") (name "/RGB_DIN") (class "Default")
      (node (ref "RGB1") (pin "DIN") (pinfunction "DIN_DIN") (pintype "passive"))
    )
    (net (code "2") (name "GND") (class "Default")
      (node (ref "C1") (pin "1") (pinfunction "1_1") (pintype "passive"))
      (node (ref "C10") (pin "1") (pinfunction "1_1") (pintype "passive"))
      (node (ref "C11") (pin "1") (pinfunction "1_1") (pintype "passive"))
      (node (ref "C12") (pin "1") (pinfunction "1_1") (pintype "passive"))
      (node (ref "C13") (pin "1") (pinfunction "1_1") (pintype "passive"))
      (node (ref "C14") (pin "1") (pinfunction "1_1") (pintype "passive"))
      (node (ref "C15") (pin "1") (pinfunction "1_1") (pintype "passive"))
      (node (ref "C16") (pin "1") (pinfunction "1_1") (pintype "passive"))
      (node (ref "C17") (pin "1") (pinfunction "1_1") (pintype "passive"))
      (node (ref "C18") (pin "1") (pinfunction "1_1") (pintype "passive"))
      (node (ref "C19") (pin "1") (pinfunction "1_1") (pintype "passive"))
      (node (ref "C2") (pin "1") (pinfunction "1_1") (pintype "passive"))
      (node (ref "C20") (pin "1") (pinfunction "1_1") (pintype "passive"))
      (node (ref "C21") (pin "1") (pinfunction "1_1") (pintype "passive"))
      (node (ref "C22") (pin "1") (pinfunction "1_1") (pintype "passive"))
      (node (ref "C23") (pin "1") (pinfunction "1_1") (pintype "passive"))
      (node (ref "C24") (pin "1") (pinfunction "1_1") (pintype "passive"))
      (node (ref "C25") (pin "1") (pinfunction "1_1") (pintype "passive"))
      (node (ref "C26") (pin "1") (pinfunction "1_1") (pintype "passive"))
      (node (ref "C27") (pin "1") (pinfunction "1_1") (pintype "passive"))
      (node (ref "C28") (pin "1") (pinfunction "1_1") (pintype "passive"))
      (node (ref "C29") (pin "1") (pinfunction "1_1") (pintype "passive"))
      (node (ref "C3") (pin "1") (pinfunction "1_1") (pintype "passive"))
      (node (ref "C30") (pin "1") (pinfunction "1_1") (pintype "passive"))
      (node (ref "C31") (pin "1") (pinfunction "1_1") (pintype "passive"))
      (node (ref "C32") (pin "1") (pinfunction "1_1") (pintype "passive"))
      (node (ref "C33") (pin "1") (pinfunction "1_1") (pintype "passive"))
      (node (ref "C34") (pin "1") (pinfunction "1_1") (pintype "passive"))
      (node (ref "C35") (pin "1") (pinfunction "1_1") (pintype "passive"))
      (node (ref "C36") (pin "1") (pinfunction "1_1") (pintype "passive"))
      (node (ref "C37") (pin "1") (pinfunction "1_1") (pintype "passive"))
      (node (ref "C38") (pin "1") (pinfunction "1_1") (pintype "passive"))
      (node (ref "C39") (pin "1") (pinfunction "1_1") (pintype "passive"))
      (node (ref "C4") (pin "1") (pinfunction "1_1") (pintype "passive"))
      (node (ref "C40") (pin "1") (pinfunction "1_1") (pintype "passive"))
      (node (ref "C41") (pin "1") (pinfunction "1_1") (pintype "passive"))
      (node (ref "C42") (pin "1") (pinfunction "1_1") (pintype "passive"))
      (node (ref "C43") (pin "1") (pinfunction "1_1") (pintype "passive"))
      (node (ref "C44") (pin "1") (pinfunction "1_1") (pintype "passive"))
      (node (ref "C45") (pin "1") (pinfunction "1_1") (pintype "passive"))
      (node (ref "C46") (pin "1") (pinfunction "1_1") (pintype "passive"))
      (node (ref "C47") (pin "1") (pinfunction "1_1") (pintype "passive"))
      (node (ref "C48") (pin "1") (pinfunction "1_1") (pintype "passive"))
      (node (ref "C49") (pin "1") (pinfunction "1_1") (pintype "passive"))
      (node (ref "C5") (pin "1") (pinfunction "1_1") (pintype "passive"))
      (node (ref "C50") (pin "1") (pinfunction "1_1") (pintype "passive"))
      (node (ref "C51") (pin "1") (pinfunction "1_1") (pintype "passive"))
      (node (ref "C52") (pin "1") (pinfunction "1_1") (pintype "passive"))
      (node (ref "C53") (pin "1") (pinfunction "1_1") (pintype "passive"))
      (node (ref "C54") (pin "1") (pinfunction "1_1") (pintype "passive"))
      (node (ref "C55") (pin "1") (pinfunction "1_1") (pintype "passive"))
      (node (ref "C56") (pin "1") (pinfunction "1_1") (pintype "passive"))
      (node (ref "C57") (pin "1") (pinfunction "1_1") (pintype "passive"))
      (node (ref "C58") (pin "1") (pinfunction "1_1") (pintype "passive"))
      (node (ref "C59") (pin "1") (pinfunction "1_1") (pintype "passive"))
      (node (ref "C6") (pin "1") (pinfunction "1_1") (pintype "passive"))
      (node (ref "C60") (pin "1") (pinfunction "1_1") (pintype "passive"))
      (node (ref "C61") (pin "1") (pinfunction "1_1") (pintype "passive"))
      (node (ref "C7") (pin "1") (pinfunction "1_1") (pintype "passive"))
      (node (ref "C8") (pin "1") (pinfunction "1_1") (pintype "passive"))
      (node (ref "C9") (pin "1") (pinfunction "1_1") (pintype "passive"))
      (node (ref "RGB1") (pin "GND") (pinfunction "GND_GND") (pintype "passive"))
      (node (ref "RGB10") (pin "GND") (pinfunction "GND_GND") (pintype "passive"))
      (node (ref "RGB11") (pin "GND") (pinfunction "GND_GND") (pintype "passive"))
      (node (ref "RGB12") (pin "GND") (pinfunction "GND_GND") (pintype "passive"))
      (node (ref "RGB13") (pin "GND") (pinfunction "GND_GND") (pintype "passive"))
      (node (ref "RGB14") (pin "GND") (pinfunction "GND_GND") (pintype "passive"))
      (node (ref "RGB15") (pin "GND") (pinfunction "GND_GND") (pintype "passive"))
      (node (ref "RGB16") (pin "GND") (pinfunction "GND_GND") (pintype "passive"))
      (node (ref "RGB17") (pin "GND") (pinfunction "GND_GND") (pintype "passive"))
      (node (ref "RGB18") (pin "GND") (pinfunction "GND_GND") (pintype "passive"))
      (node (ref "RGB19") (pin "GND") (pinfunction "GND_GND") (pintype "passive"))
      (node (ref "RGB2") (pin "GND") (pinfunction "GND_GND") (pintype "passive"))
      (node (ref "RGB20") (pin "GND") (pinfunction "GND_GND") (pintype "passive"))
      (node (ref "RGB21") (pin "GND") (pinfunction "GND_GND") (pintype "passive"))
      (node (ref "RGB22") (pin "GND") (pinfunction "GND_GND") (pintype "passive"))
      (node (ref "RGB23") (pin "GND") (pinfunction "GND_GND") (pintype "passive"))
      (node (ref "RGB24") (pin "GND") (pinfunction "GND_GND") (pintype "passive"))
      (node (ref "RGB25") (pin "GND") (pinfunction "GND_GND") (pintype "passive"))
      (node (ref "RGB26") (pin "GND") (pinfunction "GND_GND") (pintype "passive"))
      (node (ref "RGB27") (pin "GND") (pinfunction "GND_GND") (pintype "passive"))
      (node (ref "RGB28") (pin "GND") (pinfunction "GND_GND") (pintype "passive"))
      (node (ref "RGB29") (pin "GND") (pinfunction "GND_GND") (pintype "passive"))
      (node (ref "RGB3") (pin "GND") (pinfunction "GND_GND") (pintype "passive"))
      (node (ref "RGB30") (pin "GND") (pinfunction "GND_GND") (pintype "passive"))
      (node (ref "RGB31") (pin "GND") (pinfunction "GND_GND") (pintype "passive"))
      (node (ref "RGB32") (pin "GND") (pinfunction "GND_GND") (pintype "passive"))
      (node (ref "RGB33") (pin "GND") (pinfunction "GND_GND") (pintype "passive"))
      (node (ref "RGB34") (pin "GND") (pinfunction "GND_GND") (pintype "passive"))
      (node (ref "RGB35") (pin "GND") (pinfunction "GND_GND") (pintype "passive"))
      (node (ref "RGB36") (pin "GND") (pinfunction "GND_GND") (pintype "passive"))
      (node (ref "RGB37") (pin "GND") (pinfunction "GND_GND") (pintype "passive"))
      (node (ref "RGB38") (pin "GND") (pinfunction "GND_GND") (pintype "passive"))
      (node (ref "RGB39") (pin "GND") (pinfunction "GND_GND") (pintype "passive"))
      (node (ref "RGB4") (pin "GND") (pinfunction "GND_GND") (pintype "passive"))
      (node (ref "RGB40") (pin "GND") (pinfunction "GND_GND") (pintype "passive"))
      (node (ref "RGB41") (pin "GND") (pinfunction "GND_GND") (pintype "passive"))
      (node (ref "RGB42") (pin "GND") (pinfunction "GND_GND") (pintype "passive"))
      (node (ref "RGB43") (pin "GND") (pinfunction "GND_GND") (pintype "passive"))
      (node (ref "RGB44") (pin "GND") (pinfunction "GND_GND") (pintype "passive"))
      (node (ref "RGB45") (pin "GND") (pinfunction "GND_GND") (pintype "passive"))
      (node (ref "RGB46") (pin "GND") (pinfunction "GND_GND") (pintype "passive"))
      (node (ref "RGB47") (pin "GND") (pinfunction "GND_GND") (pintype "passive"))
      (node (ref "RGB48") (pin "GND") (pinfunction "GND_GND") (pintype "passive"))
      (node (ref "RGB49") (pin "GND") (pinfunction "GND_GND") (pintype "passive"))
      (node (ref "RGB5") (pin "GND") (pinfunction "GND_GND") (pintype "passive"))
      (node (ref "RGB50") (pin "GND") (pinfunction "GND_GND") (pintype "passive"))
      (node (ref "RGB51") (pin "GND") (pinfunction "GND_GND") (pintype "passive"))
      (node (ref "RGB52") (pin "GND") (pinfunction "GND_GND") (pintype "passive"))
      (node (ref "RGB53") (pin "GND") (pinfunction "GND_GND") (pintype "passive"))
      (node (ref "RGB54") (pin "GND") (pinfunction "GND_GND") (pintype "passive"))
      (node (ref "RGB55") (pin "GND") (pinfunction "GND_GND") (pintype "passive"))
      (node (ref "RGB56") (pin "GND") (pinfunction "GND_GND") (pintype "passive"))
      (node (ref "RGB57") (pin "GND") (pinfunction "GND_GND") (pintype "passive"))
      (node (ref "RGB58") (pin "GND") (pinfunction "GND_GND") (pintype "passive"))
      (node (ref "RGB59") (pin "GND") (pinfunction "GND_GND") (pintype "passive"))
      (node (ref "RGB6") (pin "GND") (pinfunction "GND_GND") (pintype "passive"))
      (node (ref "RGB60") (pin "GND") (pinfunction "GND_GND") (pintype "passive"))
      (node (ref "RGB61") (pin "GND") (pinfunction "GND_GND") (pintype "passive"))
      (node (ref "RGB7") (pin "GND") (pinfunction "GND_GND") (pintype "passive"))
      (node (ref "RGB8") (pin "GND") (pinfunction "GND_GND") (pintype "passive"))
      (node (ref "RGB9") (pin "GND") (pinfunction "GND_GND") (pintype "passive"))
    )
    (net (code "3") (name "Net-(RGB1-PadDOUT)") (class "Default")
      (node (ref "RGB1") (pin "DOUT") (pinfunction "DOUT_DOUT") (pintype "passive"))
      (node (ref "RGB2") (pin "DIN") (pinfunction "DIN_DIN") (pintype "passive"))
    )
    (net (code "4") (name "Net-(RGB2-PadDOUT)") (class "Default")
      (node (ref "RGB2") (pin "DOUT") (pinfunction "DOUT_DOUT") (pintype "passive"))
      (node (ref "RGB3") (pin "DIN") (pinfunction "DIN_DIN") (pintype "passive"))
    )
    (net (code "5") (name "Net-(RGB3-PadDOUT)") (class "Default")
      (node (ref "RGB3") (pin "DOUT") (pinfunction "DOUT_DOUT") (pintype "passive"))
      (node (ref "RGB4") (pin "DIN") (pinfunction "DIN_DIN") (pintype "passive"))
    )
    (net (code "6") (name "Net-(RGB4-PadDOUT)") (class "Default")
      (node (ref "RGB4") (pin "DOUT") (pinfunction "DOUT_DOUT") (pintype "passive"))
      (node (ref "RGB5") (pin "DIN") (pinfunction "DIN_DIN") (pintype "passive"))
    )
    (net (code "7") (name "Net-(RGB5-PadDOUT)") (class "Default")
      (node (ref "RGB5") (pin "DOUT") (pinfunction "DOUT_DOUT") (pintype "passive"))
      (node (ref "RGB6") (pin "DIN") (pinfunction "DIN_DIN") (pintype "passive"))
    )
    (net (code "8") (name "Net-(RGB6-PadDOUT)") (class "Default")
      (node (ref "RGB6") (pin "DOUT") (pinfunction "DOUT_DOUT") (pintype "passive"))
      (node (ref "RGB7") (pin "DIN") (pinfunction "DIN_DIN") (pintype "passive"))
    )
    (net (code "9") (name "Net-(RGB7-PadDOUT)") (class "Default")
      (node (ref "RGB7") (pin "DOUT") (pinfunction "DOUT_DOUT") (pintype "passive"))
      (node (ref "RGB8") (pin "DIN") (pinfunction "DIN_DIN") (pintype "passive"))
    )
    (net (code "10") (name "Net-(RGB8-PadDOUT)") (class "Default")
      (node (ref "RGB8") (pin "DOUT") (pinfunction "DOUT_DOUT") (pintype "passive"))
      (node (ref "RGB9") (pin "DIN") (pinfunction "DIN_DIN") (pintype "passive"))
    )
    (net (code "11") (name "Net-(RGB10-PadDIN)") (class "Default")
      (node (ref "RGB10") (pin "DIN") (pinfunction "DIN_DIN") (pintype "passive"))
      (node (ref "RGB9") (pin "DOUT") (pinfunction "DOUT_DOUT") (pintype "passive"))
    )
    (net (code "12") (name "Net-(RGB10-PadDOUT)") (class "Default")
      (node (ref "RGB10") (pin "DOUT") (pinfunction "DOUT_DOUT") (pintype "passive"))
      (node (ref "RGB11") (pin "DIN") (pinfunction "DIN_DIN") (pintype "passive"))
    )
    (net (code "13") (name "Net-(RGB11-PadDOUT)") (class "Default")
      (node (ref "RGB11") (pin "DOUT") (pinfunction "DOUT_DOUT") (pintype "passive"))
      (node (ref "RGB12") (pin "DIN") (pinfunction "DIN_DIN") (pintype "passive"))
    )
    (net (code "14") (name "Net-(RGB12-PadDOUT)") (class "Default")
      (node (ref "RGB12") (pin "DOUT") (pinfunction "DOUT_DOUT") (pintype "passive"))
      (node (ref "RGB13") (pin "DIN") (pinfunction "DIN_DIN") (pintype "passive"))
    )
    (net (code "15") (name "Net-(RGB13-PadDOUT)") (class "Default")
      (node (ref "RGB13") (pin "DOUT") (pinfunction "DOUT_DOUT") (pintype "passive"))
      (node (ref "RGB14") (pin "DIN") (pinfunction "DIN_DIN") (pintype "passive"))
    )
    (net (code "16") (name "Net-(RGB14-PadDOUT)") (class "Default")
      (node (ref "RGB14") (pin "DOUT") (pinfunction "DOUT_DOUT") (pintype "passive"))
      (node (ref "RGB15") (pin "DIN") (pinfunction "DIN_DIN") (pintype "passive"))
    )
    (net (code "17") (name "Net-(RGB15-PadDOUT)") (class "Default")
      (node (ref "RGB15") (pin "DOUT") (pinfunction "DOUT_DOUT") (pintype "passive"))
      (node (ref "RGB16") (pin "DIN") (pinfunction "DIN_DIN") (pintype "passive"))
    )
    (net (code "18") (name "Net-(RGB16-PadDOUT)") (class "Default")
      (node (ref "RGB16") (pin "DOUT") (pinfunction "DOUT_DOUT") (pintype "passive"))
      (node (ref "RGB17") (pin "DIN") (pinfunction "DIN_DIN") (pintype "passive"))
    )
    (net (code "19") (name "Net-(RGB17-PadDOUT)") (class "Default")
      (node (ref "RGB17") (pin "DOUT") (pinfunction "DOUT_DOUT") (pintype "passive"))
      (node (ref "RGB18") (pin "DIN") (pinfunction "DIN_DIN") (pintype "passive"))
    )
    (net (code "20") (name "Net-(RGB18-PadDOUT)") (class "Default")
      (node (ref "RGB18") (pin "DOUT") (pinfunction "DOUT_DOUT") (pintype "passive"))
      (node (ref "RGB19") (pin "DIN") (pinfunction "DIN_DIN") (pintype "passive"))
    )
    (net (code "21") (name "Net-(RGB19-PadDOUT)") (class "Default")
      (node (ref "RGB19") (pin "DOUT") (pinfunction "DOUT_DOUT") (pintype "passive"))
      (node (ref "RGB20") (pin "DIN") (pinfunction "DIN_DIN") (pintype "passive"))
    )
    (net (code "22") (name "Net-(RGB20-PadDOUT)") (class "Default")
      (node (ref "RGB20") (pin "DOUT") (pinfunction "DOUT_DOUT") (pintype "passive"))
      (node (ref "RGB21") (pin "DIN") (pinfunction "DIN_DIN") (pintype "passive"))
    )
    (net (code "23") (name "Net-(RGB21-PadDOUT)") (class "Default")
      (node (ref "RGB21") (pin "DOUT") (pinfunction "DOUT_DOUT") (pintype "passive"))
      (node (ref "RGB22") (pin "DIN") (pinfunction "DIN_DIN") (pintype "passive"))
    )
    (net (code "24") (name "Net-(RGB22-PadDOUT)") (class "Default")
      (node (ref "RGB22") (pin "DOUT") (pinfunction "DOUT_DOUT") (pintype "passive"))
      (node (ref "RGB23") (pin "DIN") (pinfunction "DIN_DIN") (pintype "passive"))
    )
    (net (code "25") (name "Net-(RGB23-PadDOUT)") (class "Default")
      (node (ref "RGB23") (pin "DOUT") (pinfunction "DOUT_DOUT") (pintype "passive"))
      (node (ref "RGB24") (pin "DIN") (pinfunction "DIN_DIN") (pintype "passive"))
    )
    (net (code "26") (name "Net-(RGB24-PadDOUT)") (class "Default")
      (node (ref "RGB24") (pin "DOUT") (pinfunction "DOUT_DOUT") (pintype "passive"))
      (node (ref "RGB25") (pin "DIN") (pinfunction "DIN_DIN") (pintype "passive"))
    )
    (net (code "27") (name "Net-(RGB25-PadDOUT)") (class "Default")
      (node (ref "RGB25") (pin "DOUT") (pinfunction "DOUT_DOUT") (pintype "passive"))
      (node (ref "RGB26") (pin "DIN") (pinfunction "DIN_DIN") (pintype "passive"))
    )
    (net (code "28") (name "Net-(RGB26-PadDOUT)") (class "Default")
      (node (ref "RGB26") (pin "DOUT") (pinfunction "DOUT_DOUT") (pintype "passive"))
      (node (ref "RGB27") (pin "DIN") (pinfunction "DIN_DIN") (pintype "passive"))
    )
    (net (code "29") (name "Net-(RGB27-PadDOUT)") (class "Default")
      (node (ref "RGB27") (pin "DOUT") (pinfunction "DOUT_DOUT") (pintype "passive"))
      (node (ref "RGB28") (pin "DIN") (pinfunction "DIN_DIN") (pintype "passive"))
    )
    (net (code "30") (name "Net-(RGB28-PadDOUT)") (class "Default")
      (node (ref "RGB28") (pin "DOUT") (pinfunction "DOUT_DOUT") (pintype "passive"))
      (node (ref "RGB29") (pin "DIN") (pinfunction "DIN_DIN") (pintype "passive"))
    )
    (net (code "31") (name "Net-(RGB29-PadDOUT)") (class "Default")
      (node (ref "RGB29") (pin "DOUT") (pinfunction "DOUT_DOUT") (pintype "passive"))
      (node (ref "RGB30") (pin "DIN") (pinfunction "DIN_DIN") (pintype "passive"))
    )
    (net (code "32") (name "Net-(RGB30-PadDOUT)") (class "Default")
      (node (ref "RGB30") (pin "DOUT") (pinfunction "DOUT_DOUT") (pintype "passive"))
      (node (ref "RGB31") (pin "DIN") (pinfunction "DIN_DIN") (pintype "passive"))
    )
    (net (code "33") (name "Net-(RGB31-PadDOUT)") (class "Default")
      (node (ref "RGB31") (pin "DOUT") (pinfunction "DOUT_DOUT") (pintype "passive"))
      (node (ref "RGB32") (pin "DIN") (pinfunction "DIN_DIN") (pintype "passive"))
    )
    (net (code "34") (name "Net-(RGB32-PadDOUT)") (class "Default")
      (node (ref "RGB32") (pin "DOUT") (pinfunction "DOUT_DOUT") (pintype "passive"))
      (node (ref "RGB33") (pin "DIN") (pinfunction "DIN_DIN") (pintype "passive"))
    )
    (net (code "35") (name "Net-(RGB33-PadDOUT)") (class "Default")
      (node (ref "RGB33") (pin "DOUT") (pinfunction "DOUT_DOUT") (pintype "passive"))
      (node (ref "RGB34") (pin "DIN") (pinfunction "DIN_DIN") (pintype "passive"))
    )
    (net (code "36") (name "Net-(RGB34-PadDOUT)") (class "Default")
      (node (ref "RGB34") (pin "DOUT") (pinfunction "DOUT_DOUT") (pintype "passive"))
      (node (ref "RGB35") (pin "DIN") (pinfunction "DIN_DIN") (pintype "passive"))
    )
    (net (code "37") (name "Net-(RGB35-PadDOUT)") (class "Default")
      (node (ref "RGB35") (pin "DOUT") (pinfunction "DOUT_DOUT") (pintype "passive"))
      (node (ref "RGB36") (pin "DIN") (pinfunction "DIN_DIN") (pintype "passive"))
    )
    (net (code "38") (name "Net-(RGB36-PadDOUT)") (class "Default")
      (node (ref "RGB36") (pin "DOUT") (pinfunction "DOUT_DOUT") (pintype "passive"))
      (node (ref "RGB37") (pin "DIN") (pinfunction "DIN_DIN") (pintype "passive"))
    )
    (net (code "39") (name "Net-(RGB37-PadDOUT)") (class "Default")
      (node (ref "RGB37") (pin "DOUT") (pinfunction "DOUT_DOUT") (pintype "passive"))
      (node (ref "RGB38") (pin "DIN") (pinfunction "DIN_DIN") (pintype "passive"))
    )
    (net (code "40") (name "Net-(RGB38-PadDOUT)") (class "Default")
      (node (ref "RGB38") (pin "DOUT") (pinfunction "DOUT_DOUT") (pintype "passive"))
      (node (ref "RGB39") (pin "DIN") (pinfunction "DIN_DIN") (pintype "passive"))
    )
    (net (code "41") (name "Net-(RGB39-PadDOUT)") (class "Default")
      (node (ref "RGB39") (pin "DOUT") (pinfunction "DOUT_DOUT") (pintype "passive"))
      (node (ref "RGB40") (pin "DIN") (pinfunction "DIN_DIN") (pintype "passive"))
    )
    (net (code "42") (name "Net-(RGB40-PadDOUT)") (class "Default")
      (node (ref "RGB40") (pin "DOUT") (pinfunction "DOUT_DOUT") (pintype "passive"))
      (node (ref "RGB41") (pin "DIN") (pinfunction "DIN_DIN") (pintype "passive"))
    )
    (net (code "43") (name "Net-(RGB41-PadDOUT)") (class "Default")
      (node (ref "RGB41") (pin "DOUT") (pinfunction "DOUT_DOUT") (pintype "passive"))
      (node (ref "RGB42") (pin "DIN") (pinfunction "DIN_DIN") (pintype "passive"))
    )
    (net (code "44") (name "Net-(RGB42-PadDOUT)") (class "Default")
      (node (ref "RGB42") (pin "DOUT") (pinfunction "DOUT_DOUT") (pintype "passive"))
      (node (ref "RGB43") (pin "DIN") (pinfunction "DIN_DIN") (pintype "passive"))
    )
    (net (code "45") (name "Net-(RGB43-PadDOUT)") (class "Default")
      (node (ref "RGB43") (pin "DOUT") (pinfunction "DOUT_DOUT") (pintype "passive"))
      (node (ref "RGB44") (pin "DIN") (pinfunction "DIN_DIN") (pintype "passive"))
    )
    (net (code "46") (name "Net-(RGB44-PadDOUT)") (class "Default")
      (node (ref "RGB44") (pin "DOUT") (pinfunction "DOUT_DOUT") (pintype "passive"))
      (node (ref "RGB45") (pin "DIN") (pinfunction "DIN_DIN") (pintype "passive"))
    )
    (net (code "47") (name "Net-(RGB45-PadDOUT)") (class "Default")
      (node (ref "RGB45") (pin "DOUT") (pinfunction "DOUT_DOUT") (pintype "passive"))
      (node (ref "RGB46") (pin "DIN") (pinfunction "DIN_DIN") (pintype "passive"))
    )
    (net (code "48") (name "Net-(RGB46-PadDOUT)") (class "Default")
      (node (ref "RGB46") (pin "DOUT") (pinfunction "DOUT_DOUT") (pintype "passive"))
      (node (ref "RGB47") (pin "DIN") (pinfunction "DIN_DIN") (pintype "passive"))
    )
    (net (code "49") (name "Net-(RGB47-PadDOUT)") (class "Default")
      (node (ref "RGB47") (pin "DOUT") (pinfunction "DOUT_DOUT") (pintype "passive"))
      (node (ref "RGB48") (pin "DIN") (pinfunction "DIN_DIN") (pintype "passive"))
    )
    (net (code "50") (name "Net-(RGB48-PadDOUT)") (class "Default")
      (node (ref "RGB48") (pin "DOUT") (pinfunction "DOUT_DOUT") (pintype "passive"))
      (node (ref "RGB49") (pin "DIN") (pinfunction "DIN_DIN") (pintype "passive"))
    )
    (net (code "51") (name "Net-(RGB49-PadDOUT)") (class "Default")
      (node (ref "RGB49") (pin "DOUT") (pinfunction "DOUT_DOUT") (pintype "passive"))
      (node (ref "RGB50") (pin "DIN") (pinfunction "DIN_DIN") (pintype "passive"))
    )
    (net (code "52") (name "Net-(RGB50-PadDOUT)") (class "Default")
      (node (ref "RGB50") (pin "DOUT") (pinfunction "DOUT_DOUT") (pintype "passive"))
      (node (ref "RGB51") (pin "DIN") (pinfunction "DIN_DIN") (pintype "passive"))
    )
    (net (code "53") (name "Net-(RGB51-PadDOUT)") (class "Default")
      (node (ref "RGB51") (pin "DOUT") (pinfunction "DOUT_DOUT") (pintype "passive"))
      (node (ref "RGB52") (pin "DIN") (pinfunction "DIN_DIN") (pintype "passive"))
    )
    (net (code "54") (name "Net-(RGB52-PadDOUT)") (class "Default")
      (node (ref "RGB52") (pin "DOUT") (pinfunction "DOUT_DOUT") (pintype "passive"))
      (node (ref "RGB53") (pin "DIN") (pinfunction "DIN_DIN") (pintype "passive"))
    )
    (net (code "55") (name "Net-(RGB53-PadDOUT)") (class "Default")
      (node (ref "RGB53") (pin "DOUT") (pinfunction "DOUT_DOUT") (pintype "passive"))
      (node (ref "RGB54") (pin "DIN") (pinfunction "DIN_DIN") (pintype "passive"))
    )
    (net (code "56") (name "Net-(RGB54-PadDOUT)") (class "Default")
      (node (ref "RGB54") (pin "DOUT") (pinfunction "DOUT_DOUT") (pintype "passive"))
      (node (ref "RGB55") (pin "DIN") (pinfunction "DIN_DIN") (pintype "passive"))
    )
    (net (code "57") (name "Net-(RGB55-PadDOUT)") (class "Default")
      (node (ref "RGB55") (pin "DOUT") (pinfunction "DOUT_DOUT") (pintype "passive"))
      (node (ref "RGB56") (pin "DIN") (pinfunction "DIN_DIN") (pintype "passive"))
    )
    (net (code "58") (name "Net-(RGB56-PadDOUT)") (class "Default")
      (node (ref "RGB56") (pin "DOUT") (pinfunction "DOUT_DOUT") (pintype "passive"))
      (node (ref "RGB57") (pin "DIN") (pinfunction "DIN_DIN") (pintype "passive"))
    )
    (net (code "59") (name "Net-(RGB57-PadDOUT)") (class "Default")
      (node (ref "RGB57") (pin "DOUT") (pinfunction "DOUT_DOUT") (pintype "passive"))
      (node (ref "RGB58") (pin "DIN") (pinfunction "DIN_DIN") (pintype "passive"))
    )
    (net (code "60") (name "Net-(RGB58-PadDOUT)") (class "Default")
      (node (ref "RGB58") (pin "DOUT") (pinfunction "DOUT_DOUT") (pintype "passive"))
      (node (ref "RGB59") (pin "DIN") (pinfunction "DIN_DIN") (pintype "passive"))
    )
    (net (code "61") (name "Net-(RGB59-PadDOUT)") (class "Default")
      (node (ref "RGB59") (pin "DOUT") (pinfunction "DOUT_DOUT") (pintype "passive"))
      (node (ref "RGB60") (pin "DIN") (pinfunction "DIN_DIN") (pintype "passive"))
    )
    (net (code "62") (name "Net-(RGB60-PadDOUT)") (class "Default")
      (node (ref "RGB60") (pin "DOUT") (pinfunction "DOUT_DOUT") (pintype "passive"))
      (node (ref "RGB61") (pin "DIN") (pinfunction "DIN_DIN") (pintype "passive"))
    )
    (net (code "63") (name "VCC") (class "Default")
      (node (ref "C1") (pin "2") (pinfunction "2_2") (pintype "passive"))
      (node (ref "C10") (pin "2") (pinfunction "2_2") (pintype "passive"))
      (node (ref "C11") (pin "2") (pinfunction "2_2") (pintype "passive"))
      (node (ref "C12") (pin "2") (pinfunction "2_2") (pintype "passive"))
      (node (ref "C13") (pin "2") (pinfunction "2_2") (pintype "passive"))
      (node (ref "C14") (pin "2") (pinfunction "2_2") (pintype "passive"))
      (node (ref "C15") (pin "2") (pinfunction "2_2") (pintype "passive"))
      (node (ref "C16") (pin "2") (pinfunction "2_2") (pintype "passive"))
      (node (ref "C17") (pin "2") (pinfunction "2_2") (pintype "passive"))
      (node (ref "C18") (pin "2") (pinfunction "2_2") (pintype "passive"))
      (node (ref "C19") (pin "2") (pinfunction "2_2") (pintype "passive"))
      (node (ref "C2") (pin "2") (pinfunction "2_2") (pintype "passive"))
      (node (ref "C20") (pin "2") (pinfunction "2_2") (pintype "passive"))
      (node (ref "C21") (pin "2") (pinfunction "2_2") (pintype "passive"))
      (node (ref "C22") (pin "2") (pinfunction "2_2") (pintype "passive"))
      (node (ref "C23") (pin "2") (pinfunction "2_2") (pintype "passive"))
      (node (ref "C24") (pin "2") (pinfunction "2_2") (pintype "passive"))
      (node (ref "C25") (pin "2") (pinfunction "2_2") (pintype "passive"))
      (node (ref "C26") (pin "2") (pinfunction "2_2") (pintype "passive"))
      (node (ref "C27") (pin "2") (pinfunction "2_2") (pintype "passive"))
      (node (ref "C28") (pin "2") (pinfunction "2_2") (pintype "passive"))
      (node (ref "C29") (pin "2") (pinfunction "2_2") (pintype "passive"))
      (node (ref "C3") (pin "2") (pinfunction "2_2") (pintype "passive"))
      (node (ref "C30") (pin "2") (pinfunction "2_2") (pintype "passive"))
      (node (ref "C31") (pin "2") (pinfunction "2_2") (pintype "passive"))
      (node (ref "C32") (pin "2") (pinfunction "2_2") (pintype "passive"))
      (node (ref "C33") (pin "2") (pinfunction "2_2") (pintype "passive"))
      (node (ref "C34") (pin "2") (pinfunction "2_2") (pintype "passive"))
      (node (ref "C35") (pin "2") (pinfunction "2_2") (pintype "passive"))
      (node (ref "C36") (pin "2") (pinfunction "2_2") (pintype "passive"))
      (node (ref "C37") (pin "2") (pinfunction "2_2") (pintype "passive"))
      (node (ref "C38") (pin "2") (pinfunction "2_2") (pintype "passive"))
      (node (ref "C39") (pin "2") (pinfunction "2_2") (pintype "passive"))
      (node (ref "C4") (pin "2") (pinfunction "2_2") (pintype "passive"))
      (node (ref "C40") (pin "2") (pinfunction "2_2") (pintype "passive"))
      (node (ref "C41") (pin "2") (pinfunction "2_2") (pintype "passive"))
      (node (ref "C42") (pin "2") (pinfunction "2_2") (pintype "passive"))
      (node (ref "C43") (pin "2") (pinfunction "2_2") (pintype "passive"))
      (node (ref "C44") (pin "2") (pinfunction "2_2") (pintype "passive"))
      (node (ref "C45") (pin "2") (pinfunction "2_2") (pintype "passive"))
      (node (ref "C46") (pin "2") (pinfunction "2_2") (pintype "passive"))
      (node (ref "C47") (pin "2") (pinfunction "2_2") (pintype "passive"))
      (node (ref "C48") (pin "2") (pinfunction "2_2") (pintype "passive"))
      (node (ref "C49") (pin "2") (pinfunction "2_2") (pintype "passive"))
      (node (ref "C5") (pin "2") (pinfunction "2_2") (pintype "passive"))
      (node (ref "C50") (pin "2") (pinfunction "2_2") (pintype "passive"))
      (node (ref "C51") (pin "2") (pinfunction "2_2") (pintype "passive"))
      (node (ref "C52") (pin "2") (pinfunction "2_2") (pintype "passive"))
      (node (ref "C53") (pin "2") (pinfunction "2_2") (pintype "passive"))
      (node (ref "C54") (pin "2") (pinfunction "2_2") (pintype "passive"))
      (node (ref "C55") (pin "2") (pinfunction "2_2") (pintype "passive"))
      (node (ref "C56") (pin "2") (pinfunction "2_2") (pintype "passive"))
      (node (ref "C57") (pin "2") (pinfunction "2_2") (pintype "passive"))
      (node (ref "C58") (pin "2") (pinfunction "2_2") (pintype "passive"))
      (node (ref "C59") (pin "2") (pinfunction "2_2") (pintype "passive"))
      (node (ref "C6") (pin "2") (pinfunction "2_2") (pintype "passive"))
      (node (ref "C60") (pin "2") (pinfunction "2_2") (pintype "passive"))
      (node (ref "C61") (pin "2") (pinfunction "2_2") (pintype "passive"))
      (node (ref "C7") (pin "2") (pinfunction "2_2") (pintype "passive"))
      (node (ref "C8") (pin "2") (pinfunction "2_2") (pintype "passive"))
      (node (ref "C9") (pin "2") (pinfunction "2_2") (pintype "passive"))
      (node (ref "RGB1") (pin "VDD") (pinfunction "VDD_VDD") (pintype "passive"))
      (node (ref "RGB10") (pin "VDD") (pinfunction "VDD_VDD") (pintype "passive"))
      (node (ref "RGB11") (pin "VDD") (pinfunction "VDD_VDD") (pintype "passive"))
      (node (ref "RGB12") (pin "VDD") (pinfunction "VDD_VDD") (pintype "passive"))
      (node (ref "RGB13") (pin "VDD") (pinfunction "VDD_VDD") (pintype "passive"))
      (node (ref "RGB14") (pin "VDD") (pinfunction "VDD_VDD") (pintype "passive"))
      (node (ref "RGB15") (pin "VDD") (pinfunction "VDD_VDD") (pintype "passive"))
      (node (ref "RGB16") (pin "VDD") (pinfunction "VDD_VDD") (pintype "passive"))
      (node (ref "RGB17") (pin "VDD") (pinfunction "VDD_VDD") (pintype "passive"))
      (node (ref "RGB18") (pin "VDD") (pinfunction "VDD_VDD") (pintype "passive"))
      (node (ref "RGB19") (pin "VDD") (pinfunction "VDD_VDD") (pintype "passive"))
      (node (ref "RGB2") (pin "VDD") (pinfunction "VDD_VDD") (pintype "passive"))
      (node (ref "RGB20") (pin "VDD") (pinfunction "VDD_VDD") (pintype "passive"))
      (node (ref "RGB21") (pin "VDD") (pinfunction "VDD_VDD") (pintype "passive"))
      (node (ref "RGB22") (pin "VDD") (pinfunction "VDD_VDD") (pintype "passive"))
      (node (ref "RGB23") (pin "VDD") (pinfunction "VDD_VDD") (pintype "passive"))
      (node (ref "RGB24") (pin "VDD") (pinfunction "VDD_VDD") (pintype "passive"))
      (node (ref "RGB25") (pin "VDD") (pinfunction "VDD_VDD") (pintype "passive"))
      (node (ref "RGB26") (pin "VDD") (pinfunction "VDD_VDD") (pintype "passive"))
      (node (ref "RGB27") (pin "VDD") (pinfunction "VDD_VDD") (pintype "passive"))
      (node (ref "RGB28") (pin "VDD") (pinfunction "VDD_VDD") (pintype "passive"))
      (node (ref "RGB29") (pin "VDD") (pinfunction "VDD_VDD") (pintype "passive"))
      (node (ref "RGB3") (pin "VDD") (pinfunction "VDD_VDD") (pintype "passive"))
      (node (ref "RGB30") (pin "VDD") (pinfunction "VDD_VDD") (pintype "passive"))
      (node (ref "RGB31") (pin "VDD") (pinfunction "VDD_VDD") (pintype "passive"))
      (node (ref "RGB32") (pin "VDD") (pinfunction "VDD_VDD") (pintype "passive"))
      (node (ref "RGB33") (pin "VDD") (pinfunction "VDD_VDD") (pintype "passive"))
      (node (ref "RGB34") (pin "VDD") (pinfunction "VDD_VDD") (pintype "passive"))
      (node (ref "RGB35") (pin "VDD") (pinfunction "VDD_VDD") (pintype "passive"))
      (node (ref "RGB36") (pin "VDD") (pinfunction "VDD_VDD") (pintype "passive"))
      (node (ref "RGB37") (pin "VDD") (pinfunction "VDD_VDD") (pintype "passive"))
      (node (ref "RGB38") (pin "VDD") (pinfunction "VDD_VDD") (pintype "passive"))
      (node (ref "RGB39") (pin "VDD") (pinfunction "VDD_VDD") (pintype "passive"))
      (node (ref "RGB4") (pin "VDD") (pinfunction "VDD_VDD") (pintype "passive"))
      (node (ref "RGB40") (pin "VDD") (pinfunction "VDD_VDD") (pintype "passive"))
      (node (ref "RGB41") (pin "VDD") (pinfunction "VDD_VDD") (pintype "passive"))
      (node (ref "RGB42") (pin "VDD") (pinfunction "VDD_VDD") (pintype "passive"))
      (node (ref "RGB43") (pin "VDD") (pinfunction "VDD_VDD") (pintype "passive"))
      (node (ref "RGB44") (pin "VDD") (pinfunction "VDD_VDD") (pintype "passive"))
      (node (ref "RGB45") (pin "VDD") (pinfunction "VDD_VDD") (pintype "passive"))
      (node (ref "RGB46") (pin "VDD") (pinfunction "VDD_VDD") (pintype "passive"))
      (node (ref "RGB47") (pin "VDD") (pinfunction "VDD_VDD") (pintype "passive"))
      (node (ref "RGB48") (pin "VDD") (pinfunction "VDD_VDD") (pintype "passive"))
      (node (ref "RGB49") (pin "VDD") (pinfunction "VDD_VDD") (pintype "passive"))
      (node (ref "RGB5") (pin "VDD") (pinfunction "VDD_VDD") (pintype "passive"))
      (node (ref "RGB50") (pin "VDD") (pinfunction "VDD_VDD") (pintype "passive"))
      (node (ref "RGB51") (pin "VDD") (pinfunction "VDD_VDD") (pintype "passive"))
      (node (ref "RGB52") (pin "VDD") (pinfunction "VDD_VDD") (pintype "passive"))
      (node (ref "RGB53") (pin "VDD") (pinfunction "VDD_VDD") (pintype "passive"))
      (node (ref "RGB54") (pin "VDD") (pinfunction "VDD_VDD") (pintype "passive"))
      (node (ref "RGB55") (pin "VDD") (pinfunction "VDD_VDD") (pintype "passive"))
      (node (ref "RGB56") (pin "VDD") (pinfunction "VDD_VDD") (pintype "passive"))
      (node (ref "RGB57") (pin "VDD") (pinfunction "VDD_VDD") (pintype "passive"))
      (node (ref "RGB58") (pin "VDD") (pinfunction "VDD_VDD") (pintype "passive"))
      (node (ref "RGB59") (pin "VDD") (pinfunction "VDD_VDD") (pintype "passive"))
      (node (ref "RGB6") (pin "VDD") (pinfunction "VDD_VDD") (pintype "passive"))
      (node (ref "RGB60") (pin "VDD") (pinfunction "VDD_VDD") (pintype "passive"))
      (node (ref "RGB61") (pin "VDD") (pinfunction "VDD_VDD") (pintype "passive"))
      (node (ref "RGB7") (pin "VDD") (pinfunction "VDD_VDD") (pintype "passive"))
      (node (ref "RGB8") (pin "VDD") (pinfunction "VDD_VDD") (pintype "passive"))
      (node (ref "RGB9") (pin "VDD") (pinfunction "VDD_VDD") (pintype "passive"))
    )
    (net (code "64") (name "unconnected-(RGB61-PadDOUT)") (class "Default")
      (node (ref "RGB61") (pin "DOUT") (pinfunction "DOUT_DOUT") (pintype "passive"))
    )
  )
)
